# F407VET6.net
KiCad netlist of a schematic drawn in Altium Designer
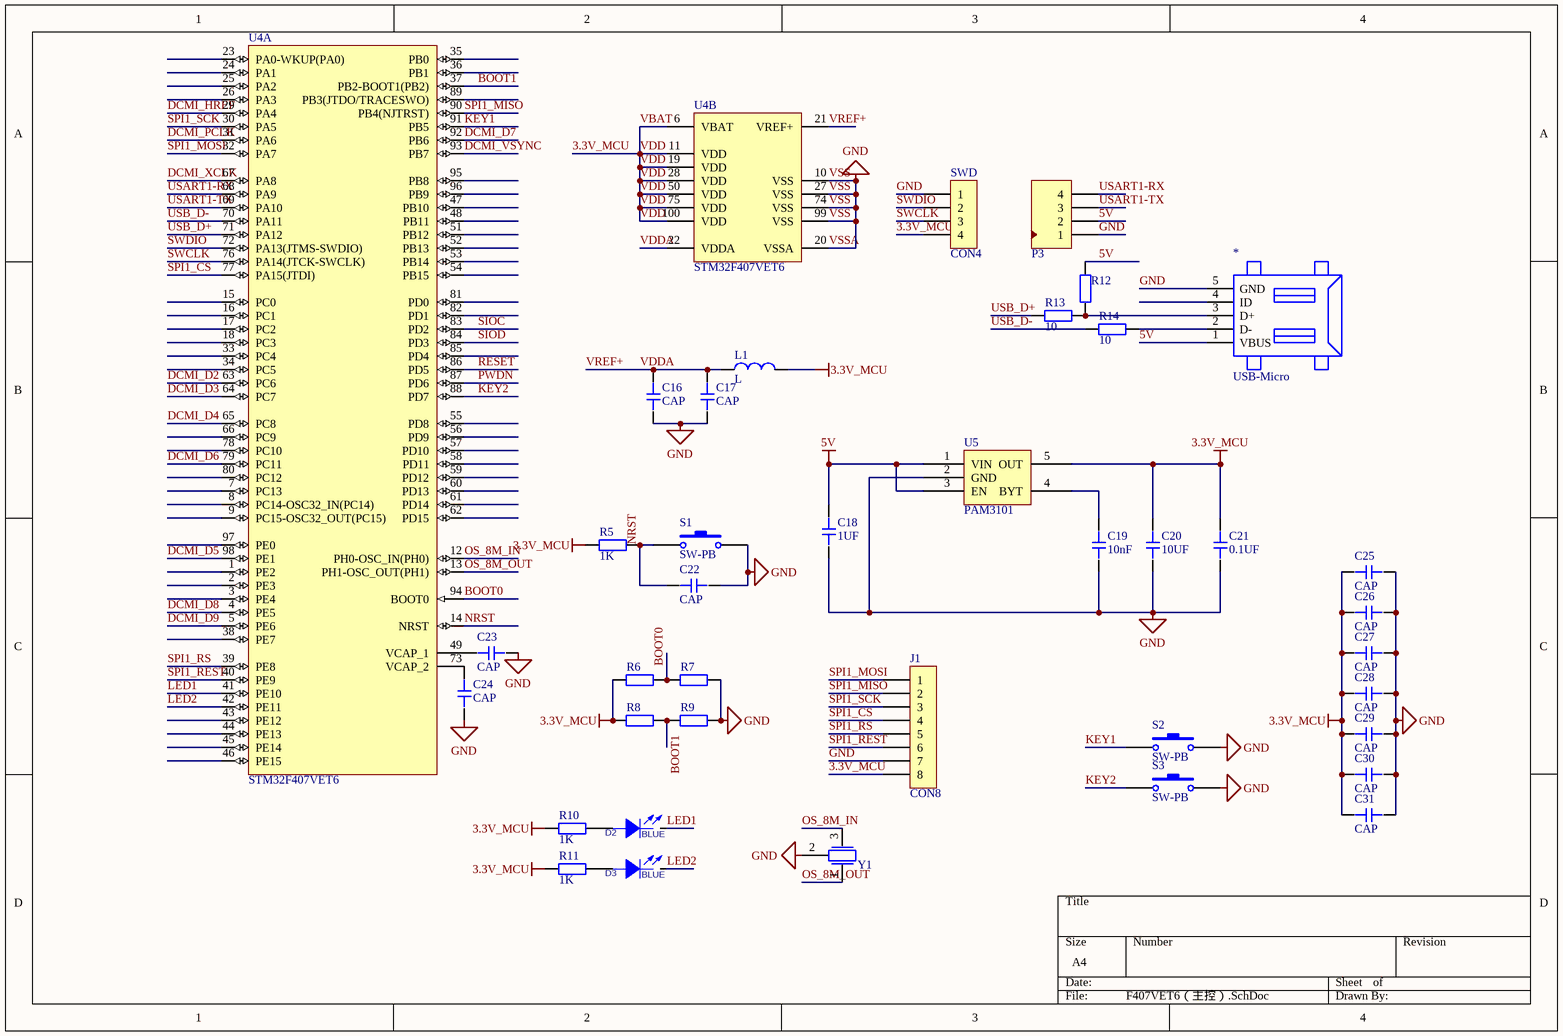
[diagram p0: F407VET6（主控）.SchDoc]

(export (version "E")
  (design (tool "Eeschema 10.0.6"))
  (components
    (comp (ref "*")
      (value "USB-Micro")
      (footprint "USB-Micro")
      (libsource (lib "XJDYJB-v1.24") (part "USB-Micro"))
    )
    (comp (ref "C16") (value "CAP") (footprint "C_0603") (libsource (lib "XJDYJB-v1.24") (part "CAP")))
    (comp (ref "C17") (value "CAP") (footprint "C_0603") (libsource (lib "XJDYJB-v1.24") (part "CAP")))
    (comp (ref "C18") (value "1UF") (footprint "C_0603") (libsource (lib "XJDYJB-v1.24") (part "CAP")))
    (comp (ref "C19") (value "10nF") (footprint "C_0603") (libsource (lib "XJDYJB-v1.24") (part "CAP")))
    (comp (ref "C20") (value "10UF") (footprint "C_0805") (libsource (lib "XJDYJB-v1.24") (part "CAP")))
    (comp (ref "C21") (value "0.1UF") (footprint "C_0603") (libsource (lib "XJDYJB-v1.24") (part "CAP")))
    (comp (ref "C22") (value "CAP") (footprint "C_0603") (libsource (lib "XJDYJB-v1.24") (part "CAP")))
    (comp (ref "C23") (value "CAP") (footprint "C_0603") (libsource (lib "XJDYJB-v1.24") (part "CAP")))
    (comp (ref "C24") (value "CAP") (footprint "C_0603") (libsource (lib "XJDYJB-v1.24") (part "CAP")))
    (comp (ref "C25") (value "CAP") (footprint "C_0603") (libsource (lib "XJDYJB-v1.24") (part "CAP")))
    (comp (ref "C26") (value "CAP") (footprint "C_0603") (libsource (lib "XJDYJB-v1.24") (part "CAP")))
    (comp (ref "C27") (value "CAP") (footprint "C_0603") (libsource (lib "XJDYJB-v1.24") (part "CAP")))
    (comp (ref "C28") (value "CAP") (footprint "C_0603") (libsource (lib "XJDYJB-v1.24") (part "CAP")))
    (comp (ref "C29") (value "CAP") (footprint "C_0603") (libsource (lib "XJDYJB-v1.24") (part "CAP")))
    (comp (ref "C30") (value "CAP") (footprint "C_0603") (libsource (lib "XJDYJB-v1.24") (part "CAP")))
    (comp (ref "C31") (value "CAP") (footprint "C_0603") (libsource (lib "XJDYJB-v1.24") (part "CAP")))
    (comp (ref "D2")
      (value "BLUE")
      (footprint "LED_0603")
      (fields (field (name "Comment") "LED"))
      (libsource (lib "XJDYJB-v1.24") (part "LED"))
    )
    (comp (ref "D3")
      (value "BLUE")
      (footprint "LED_0603")
      (fields (field (name "Comment") "LED"))
      (libsource (lib "XJDYJB-v1.24") (part "LED"))
    )
    (comp (ref "J1")
      (value "CON8")
      (footprint "sip-8")
      (description "Connector")
      (libsource (lib "接口") (part "CON8"))
    )
    (comp (ref "L1") (value "L") (footprint "L-0603") (libsource (lib "XJDYJB-v1.24") (part "L")))
    (comp (ref "P3")
      (value "Header 4")
      (footprint "HDR4*1_SH1.0")
      (description "接插件")
      (fields (field (name "PUBLISHER") "Altium Limited"))
      (libsource (lib "HDR_Fszhang") (part "Header 4"))
    )
    (comp (ref "R5")
      (value "1K")
      (footprint "0603-1")
      (description "贴片电阻")
      (fields (field (name "Comment") "Res1") (field (name "PUBLISHER") "Altium Limited"))
      (libsource (lib "Fszhang") (part "Res1"))
    )
    (comp (ref "R6")
      (value "Res1")
      (footprint "0603-1")
      (description "贴片电阻")
      (fields (field (name "PUBLISHER") "Altium Limited"))
      (libsource (lib "Fszhang") (part "Res1"))
    )
    (comp (ref "R7")
      (value "Res1")
      (footprint "0603-1")
      (description "贴片电阻")
      (fields (field (name "PUBLISHER") "Altium Limited"))
      (libsource (lib "Fszhang") (part "Res1"))
    )
    (comp (ref "R8")
      (value "Res1")
      (footprint "0603-1")
      (description "贴片电阻")
      (fields (field (name "PUBLISHER") "Altium Limited"))
      (libsource (lib "Fszhang") (part "Res1"))
    )
    (comp (ref "R9")
      (value "Res1")
      (footprint "0603-1")
      (description "贴片电阻")
      (fields (field (name "PUBLISHER") "Altium Limited"))
      (libsource (lib "Fszhang") (part "Res1"))
    )
    (comp (ref "R10")
      (value "1K")
      (footprint "0603-1")
      (description "贴片电阻")
      (fields (field (name "Comment") "Res1") (field (name "PUBLISHER") "Altium Limited"))
      (libsource (lib "Fszhang") (part "Res1"))
    )
    (comp (ref "R11")
      (value "1K")
      (footprint "0603-1")
      (description "贴片电阻")
      (fields (field (name "Comment") "Res1") (field (name "PUBLISHER") "Altium Limited"))
      (libsource (lib "Fszhang") (part "Res1"))
    )
    (comp (ref "R12")
      (value "Res1")
      (footprint "0603-1")
      (description "贴片电阻")
      (fields (field (name "PUBLISHER") "Altium Limited"))
      (libsource (lib "") (part "Res1_1"))
    )
    (comp (ref "R13")
      (value "10")
      (footprint "0603-1")
      (description "贴片电阻")
      (fields (field (name "Comment") "Res1") (field (name "PUBLISHER") "Altium Limited"))
      (libsource (lib "Fszhang") (part "Res1"))
    )
    (comp (ref "R14")
      (value "10")
      (footprint "0603-1")
      (description "贴片电阻")
      (fields (field (name "Comment") "Res1") (field (name "PUBLISHER") "Altium Limited"))
      (libsource (lib "Fszhang") (part "Res1"))
    )
    (comp (ref "S1")
      (value "SW-PB")
      (footprint "Switch-PB-C-M")
      (description "Switch")
      (fields (field (name "PUBLISHER") "Altium Limited"))
      (libsource (lib "门控服务器库文件") (part "SW-PB"))
    )
    (comp (ref "S2")
      (value "SW-PB")
      (footprint "Switch-PB-C-M")
      (description "Switch")
      (fields (field (name "PUBLISHER") "Altium Limited"))
      (libsource (lib "门控服务器库文件") (part "SW-PB"))
    )
    (comp (ref "S3")
      (value "SW-PB")
      (footprint "Switch-PB-C-M")
      (description "Switch")
      (fields (field (name "PUBLISHER") "Altium Limited"))
      (libsource (lib "门控服务器库文件") (part "SW-PB"))
    )
    (comp (ref "SWD")
      (value "CON4")
      (footprint "sip-4")
      (description "Connector")
      (libsource (lib "接口") (part "CON4"))
    )
    (comp (ref "U4")
      (value "STM32F407VET6")
      (footprint "STM-LQFP100_N")
      (fields (field (name "MANUFACTURER") "STMicroelectronics"))
      (libsource (lib "STMicroelectronics STM32 F4") (part "STM32F407VET6"))
    )
    (comp (ref "U5")
      (value "PAM3101")
      (footprint "SOT23-5")
      (description "LDO")
      (libsource (lib "XJDYJB-v1.24") (part "PAM3101"))
    )
    (comp (ref "Y1")
      (value "XTAL-3PIN")
      (footprint "X-CPX20")
      (description "贴片晶振")
      (libsource (lib "Fszhang") (part "XTAL-3PIN"))
    )
  )
  (nets
    (net (code "1") (name "/BOOT0") (class "Default")
      (node (ref "R6") (pin "2") (pinfunction "2_2") (pintype "passive"))
      (node (ref "R7") (pin "1") (pinfunction "1_1") (pintype "passive"))
      (node (ref "U4") (pin "94") (pinfunction "BOOT0_94") (pintype "input"))
    )
    (net (code "2") (name "/BOOT1") (class "Default")
      (node (ref "R8") (pin "2") (pinfunction "2_2") (pintype "passive"))
      (node (ref "R9") (pin "1") (pinfunction "1_1") (pintype "passive"))
      (node (ref "U4") (pin "37") (pinfunction "PB2-BOOT1(PB2)_37") (pintype "bidirectional"))
    )
    (net (code "3") (name "/DCMI_D2") (class "Default")
      (node (ref "U4") (pin "63") (pinfunction "PC6_63") (pintype "bidirectional"))
    )
    (net (code "4") (name "/DCMI_D3") (class "Default")
      (node (ref "U4") (pin "64") (pinfunction "PC7_64") (pintype "bidirectional"))
    )
    (net (code "5") (name "/DCMI_D4") (class "Default")
      (node (ref "U4") (pin "65") (pinfunction "PC8_65") (pintype "bidirectional"))
    )
    (net (code "6") (name "/DCMI_D5") (class "Default")
      (node (ref "U4") (pin "98") (pinfunction "PE1_98") (pintype "bidirectional"))
    )
    (net (code "7") (name "/DCMI_D6") (class "Default")
      (node (ref "U4") (pin "79") (pinfunction "PC11_79") (pintype "bidirectional"))
    )
    (net (code "8") (name "/DCMI_D7") (class "Default")
      (node (ref "U4") (pin "92") (pinfunction "PB6_92") (pintype "bidirectional"))
    )
    (net (code "9") (name "/DCMI_D8") (class "Default")
      (node (ref "U4") (pin "4") (pinfunction "PE5_4") (pintype "bidirectional"))
    )
    (net (code "10") (name "/DCMI_D9") (class "Default")
      (node (ref "U4") (pin "5") (pinfunction "PE6_5") (pintype "bidirectional"))
    )
    (net (code "11") (name "/DCMI_HREF") (class "Default")
      (node (ref "U4") (pin "29") (pinfunction "PA4_29") (pintype "bidirectional"))
    )
    (net (code "12") (name "/DCMI_PCLK") (class "Default")
      (node (ref "U4") (pin "31") (pinfunction "PA6_31") (pintype "bidirectional"))
    )
    (net (code "13") (name "/DCMI_VSYNC") (class "Default")
      (node (ref "U4") (pin "93") (pinfunction "PB7_93") (pintype "bidirectional"))
    )
    (net (code "14") (name "/DCMI_XCLK") (class "Default")
      (node (ref "U4") (pin "67") (pinfunction "PA8_67") (pintype "bidirectional"))
    )
    (net (code "15") (name "/KEY1") (class "Default")
      (node (ref "S2") (pin "1") (pinfunction "1_1") (pintype "passive"))
      (node (ref "U4") (pin "91") (pinfunction "PB5_91") (pintype "bidirectional"))
    )
    (net (code "16") (name "/KEY2") (class "Default")
      (node (ref "S3") (pin "1") (pinfunction "1_1") (pintype "passive"))
      (node (ref "U4") (pin "88") (pinfunction "PD7_88") (pintype "bidirectional"))
    )
    (net (code "17") (name "/LED1") (class "Default")
      (node (ref "D2") (pin "2") (pinfunction "CATHODE_2") (pintype "passive"))
      (node (ref "U4") (pin "41") (pinfunction "PE10_41") (pintype "bidirectional"))
    )
    (net (code "18") (name "/LED2") (class "Default")
      (node (ref "D3") (pin "2") (pinfunction "CATHODE_2") (pintype "passive"))
      (node (ref "U4") (pin "42") (pinfunction "PE11_42") (pintype "bidirectional"))
    )
    (net (code "19") (name "/NRST") (class "Default")
      (node (ref "C22") (pin "2") (pinfunction "2_2") (pintype "passive"))
      (node (ref "R5") (pin "2") (pinfunction "2_2") (pintype "passive"))
      (node (ref "S1") (pin "1") (pinfunction "1_1") (pintype "passive"))
      (node (ref "U4") (pin "14") (pinfunction "NRST_14") (pintype "bidirectional"))
    )
    (net (code "20") (name "/OS_8M_IN") (class "Default")
      (node (ref "U4") (pin "12") (pinfunction "PH0-OSC_IN(PH0)_12") (pintype "bidirectional"))
      (node (ref "Y1") (pin "3") (pinfunction "3_3") (pintype "passive"))
    )
    (net (code "21") (name "/OS_8M_OUT") (class "Default")
      (node (ref "U4") (pin "13") (pinfunction "PH1-OSC_OUT(PH1)_13") (pintype "bidirectional"))
      (node (ref "Y1") (pin "1") (pinfunction "1_1") (pintype "passive"))
    )
    (net (code "22") (name "/PWDN") (class "Default")
      (node (ref "U4") (pin "87") (pinfunction "PD6_87") (pintype "bidirectional"))
    )
    (net (code "23") (name "/RESET") (class "Default")
      (node (ref "U4") (pin "86") (pinfunction "PD5_86") (pintype "bidirectional"))
    )
    (net (code "24") (name "/SIOC") (class "Default")
      (node (ref "U4") (pin "83") (pinfunction "PD2_83") (pintype "bidirectional"))
    )
    (net (code "25") (name "/SIOD") (class "Default")
      (node (ref "U4") (pin "84") (pinfunction "PD3_84") (pintype "bidirectional"))
    )
    (net (code "26") (name "/SPI1_CS") (class "Default")
      (node (ref "J1") (pin "4") (pinfunction "4_4") (pintype "passive"))
      (node (ref "U4") (pin "77") (pinfunction "PA15(JTDI)_77") (pintype "bidirectional"))
    )
    (net (code "27") (name "/SPI1_MISO") (class "Default")
      (node (ref "J1") (pin "2") (pinfunction "2_2") (pintype "passive"))
      (node (ref "U4") (pin "90") (pinfunction "PB4(NJTRST)_90") (pintype "bidirectional"))
    )
    (net (code "28") (name "/SPI1_MOSI") (class "Default")
      (node (ref "J1") (pin "1") (pinfunction "1_1") (pintype "passive"))
      (node (ref "U4") (pin "32") (pinfunction "PA7_32") (pintype "bidirectional"))
    )
    (net (code "29") (name "/SPI1_REST") (class "Default")
      (node (ref "J1") (pin "6") (pinfunction "6_6") (pintype "passive"))
      (node (ref "U4") (pin "40") (pinfunction "PE9_40") (pintype "bidirectional"))
    )
    (net (code "30") (name "/SPI1_RS") (class "Default")
      (node (ref "J1") (pin "5") (pinfunction "5_5") (pintype "passive"))
      (node (ref "U4") (pin "39") (pinfunction "PE8_39") (pintype "bidirectional"))
    )
    (net (code "31") (name "/SPI1_SCK") (class "Default")
      (node (ref "J1") (pin "3") (pinfunction "3_3") (pintype "passive"))
      (node (ref "U4") (pin "30") (pinfunction "PA5_30") (pintype "bidirectional"))
    )
    (net (code "32") (name "/SWCLK") (class "Default")
      (node (ref "SWD") (pin "3") (pinfunction "3_3") (pintype "passive"))
      (node (ref "U4") (pin "76") (pinfunction "PA14(JTCK-SWCLK)_76") (pintype "bidirectional"))
    )
    (net (code "33") (name "/SWDIO") (class "Default")
      (node (ref "SWD") (pin "2") (pinfunction "2_2") (pintype "passive"))
      (node (ref "U4") (pin "72") (pinfunction "PA13(JTMS-SWDIO)_72") (pintype "bidirectional"))
    )
    (net (code "34") (name "/USART1-RX") (class "Default")
      (node (ref "P3") (pin "4") (pinfunction "4_4") (pintype "passive"))
      (node (ref "U4") (pin "68") (pinfunction "PA9_68") (pintype "bidirectional"))
    )
    (net (code "35") (name "/USART1-TX") (class "Default")
      (node (ref "P3") (pin "3") (pinfunction "3_3") (pintype "passive"))
      (node (ref "U4") (pin "69") (pinfunction "PA10_69") (pintype "bidirectional"))
    )
    (net (code "36") (name "/USB_D+") (class "Default")
      (node (ref "R13") (pin "1") (pinfunction "1_1") (pintype "passive"))
      (node (ref "U4") (pin "71") (pinfunction "PA12_71") (pintype "bidirectional"))
    )
    (net (code "37") (name "/USB_D-") (class "Default")
      (node (ref "R14") (pin "1") (pinfunction "1_1") (pintype "passive"))
      (node (ref "U4") (pin "70") (pinfunction "PA11_70") (pintype "bidirectional"))
    )
    (net (code "38") (name "/VDDA") (class "Default")
      (node (ref "C16") (pin "2") (pinfunction "2_2") (pintype "passive"))
      (node (ref "C17") (pin "2") (pinfunction "2_2") (pintype "passive"))
      (node (ref "L1") (pin "1") (pinfunction "1_1") (pintype "passive"))
      (node (ref "U4") (pin "21") (pinfunction "VREF+_21") (pintype "power_in"))
      (node (ref "U4") (pin "22") (pinfunction "VDDA_22") (pintype "power_in"))
    )
    (net (code "39") (name "3.3V_MCU") (class "Default")
      (node (ref "C20") (pin "2") (pinfunction "2_2") (pintype "passive"))
      (node (ref "C21") (pin "2") (pinfunction "2_2") (pintype "passive"))
      (node (ref "C25") (pin "2") (pinfunction "2_2") (pintype "passive"))
      (node (ref "C26") (pin "2") (pinfunction "2_2") (pintype "passive"))
      (node (ref "C27") (pin "2") (pinfunction "2_2") (pintype "passive"))
      (node (ref "C28") (pin "2") (pinfunction "2_2") (pintype "passive"))
      (node (ref "C29") (pin "2") (pinfunction "2_2") (pintype "passive"))
      (node (ref "C30") (pin "2") (pinfunction "2_2") (pintype "passive"))
      (node (ref "C31") (pin "2") (pinfunction "2_2") (pintype "passive"))
      (node (ref "J1") (pin "8") (pinfunction "8_8") (pintype "passive"))
      (node (ref "L1") (pin "2") (pinfunction "2_2") (pintype "passive"))
      (node (ref "R10") (pin "1") (pinfunction "1_1") (pintype "passive"))
      (node (ref "R11") (pin "1") (pinfunction "1_1") (pintype "passive"))
      (node (ref "R5") (pin "1") (pinfunction "1_1") (pintype "passive"))
      (node (ref "R6") (pin "1") (pinfunction "1_1") (pintype "passive"))
      (node (ref "R8") (pin "1") (pinfunction "1_1") (pintype "passive"))
      (node (ref "SWD") (pin "4") (pinfunction "4_4") (pintype "passive"))
      (node (ref "U4") (pin "100") (pinfunction "VDD_100") (pintype "power_in"))
      (node (ref "U4") (pin "11") (pinfunction "VDD_11") (pintype "power_in"))
      (node (ref "U4") (pin "19") (pinfunction "VDD_19") (pintype "power_in"))
      (node (ref "U4") (pin "28") (pinfunction "VDD_28") (pintype "power_in"))
      (node (ref "U4") (pin "50") (pinfunction "VDD_50") (pintype "power_in"))
      (node (ref "U4") (pin "6") (pinfunction "VBAT_6") (pintype "power_in"))
      (node (ref "U4") (pin "75") (pinfunction "VDD_75") (pintype "power_in"))
      (node (ref "U5") (pin "5") (pinfunction "OUT_5") (pintype "passive"))
    )
    (net (code "40") (name "5V") (class "Default")
      (node (ref "*") (pin "1") (pinfunction "VBUS_1") (pintype "passive"))
      (node (ref "C18") (pin "2") (pinfunction "2_2") (pintype "passive"))
      (node (ref "P3") (pin "2") (pinfunction "2_2") (pintype "passive"))
      (node (ref "R12") (pin "2") (pinfunction "2_2") (pintype "passive"))
      (node (ref "U5") (pin "1") (pinfunction "VIN_1") (pintype "passive"))
      (node (ref "U5") (pin "3") (pinfunction "EN_3") (pintype "passive"))
    )
    (net (code "41") (name "GND") (class "Default")
      (node (ref "*") (pin "5") (pinfunction "GND_5") (pintype "passive"))
      (node (ref "C16") (pin "1") (pinfunction "1_1") (pintype "passive"))
      (node (ref "C17") (pin "1") (pinfunction "1_1") (pintype "passive"))
      (node (ref "C18") (pin "1") (pinfunction "1_1") (pintype "passive"))
      (node (ref "C19") (pin "1") (pinfunction "1_1") (pintype "passive"))
      (node (ref "C20") (pin "1") (pinfunction "1_1") (pintype "passive"))
      (node (ref "C21") (pin "1") (pinfunction "1_1") (pintype "passive"))
      (node (ref "C22") (pin "1") (pinfunction "1_1") (pintype "passive"))
      (node (ref "C23") (pin "1") (pinfunction "1_1") (pintype "passive"))
      (node (ref "C24") (pin "2") (pinfunction "2_2") (pintype "passive"))
      (node (ref "C25") (pin "1") (pinfunction "1_1") (pintype "passive"))
      (node (ref "C26") (pin "1") (pinfunction "1_1") (pintype "passive"))
      (node (ref "C27") (pin "1") (pinfunction "1_1") (pintype "passive"))
      (node (ref "C28") (pin "1") (pinfunction "1_1") (pintype "passive"))
      (node (ref "C29") (pin "1") (pinfunction "1_1") (pintype "passive"))
      (node (ref "C30") (pin "1") (pinfunction "1_1") (pintype "passive"))
      (node (ref "C31") (pin "1") (pinfunction "1_1") (pintype "passive"))
      (node (ref "J1") (pin "7") (pinfunction "7_7") (pintype "passive"))
      (node (ref "P3") (pin "1") (pinfunction "1_1") (pintype "passive"))
      (node (ref "R7") (pin "2") (pinfunction "2_2") (pintype "passive"))
      (node (ref "R9") (pin "2") (pinfunction "2_2") (pintype "passive"))
      (node (ref "S1") (pin "2") (pinfunction "2_2") (pintype "passive"))
      (node (ref "S2") (pin "2") (pinfunction "2_2") (pintype "passive"))
      (node (ref "S3") (pin "2") (pinfunction "2_2") (pintype "passive"))
      (node (ref "SWD") (pin "1") (pinfunction "1_1") (pintype "passive"))
      (node (ref "U4") (pin "10") (pinfunction "VSS_10") (pintype "power_in"))
      (node (ref "U4") (pin "20") (pinfunction "VSSA_20") (pintype "power_in"))
      (node (ref "U4") (pin "27") (pinfunction "VSS_27") (pintype "power_in"))
      (node (ref "U4") (pin "74") (pinfunction "VSS_74") (pintype "power_in"))
      (node (ref "U4") (pin "99") (pinfunction "VSS_99") (pintype "power_in"))
      (node (ref "U5") (pin "2") (pinfunction "GND_2") (pintype "passive"))
      (node (ref "Y1") (pin "2") (pinfunction "2_2") (pintype "passive"))
    )
    (net (code "42") (name "Net-(*-D+)") (class "Default")
      (node (ref "*") (pin "3") (pinfunction "D+_3") (pintype "passive"))
      (node (ref "R12") (pin "1") (pinfunction "1_1") (pintype "passive"))
      (node (ref "R13") (pin "2") (pinfunction "2_2") (pintype "passive"))
    )
    (net (code "43") (name "Net-(*-D-)") (class "Default")
      (node (ref "*") (pin "2") (pinfunction "D-_2") (pintype "passive"))
      (node (ref "R14") (pin "2") (pinfunction "2_2") (pintype "passive"))
    )
    (net (code "44") (name "Net-(D2-ANODE)") (class "Default")
      (node (ref "D2") (pin "1") (pinfunction "ANODE_1") (pintype "passive"))
      (node (ref "R10") (pin "2") (pinfunction "2_2") (pintype "passive"))
    )
    (net (code "45") (name "Net-(D3-ANODE)") (class "Default")
      (node (ref "D3") (pin "1") (pinfunction "ANODE_1") (pintype "passive"))
      (node (ref "R11") (pin "2") (pinfunction "2_2") (pintype "passive"))
    )
    (net (code "46") (name "Net-(U4A-VCAP_1)") (class "Default")
      (node (ref "C23") (pin "2") (pinfunction "2_2") (pintype "passive"))
      (node (ref "U4") (pin "49") (pinfunction "VCAP_1_49") (pintype "power_in"))
    )
    (net (code "47") (name "Net-(U4A-VCAP_2)") (class "Default")
      (node (ref "C24") (pin "1") (pinfunction "1_1") (pintype "passive"))
      (node (ref "U4") (pin "73") (pinfunction "VCAP_2_73") (pintype "power_in"))
    )
    (net (code "48") (name "Net-(U5-BYT)") (class "Default")
      (node (ref "C19") (pin "2") (pinfunction "2_2") (pintype "passive"))
      (node (ref "U5") (pin "4") (pinfunction "BYT_4") (pintype "passive"))
    )
    (net (code "49") (name "unconnected-(*-ID-Pad4)") (class "Default")
      (node (ref "*") (pin "4") (pinfunction "ID_4") (pintype "passive"))
    )
    (net (code "50") (name "unconnected-(U4A-PA0-WKUP(PA0)-Pad23)") (class "Default")
      (node (ref "U4") (pin "23") (pinfunction "PA0-WKUP(PA0)_23") (pintype "bidirectional"))
    )
    (net (code "51") (name "unconnected-(U4A-PA1-Pad24)") (class "Default")
      (node (ref "U4") (pin "24") (pinfunction "PA1_24") (pintype "bidirectional"))
    )
    (net (code "52") (name "unconnected-(U4A-PA2-Pad25)") (class "Default")
      (node (ref "U4") (pin "25") (pinfunction "PA2_25") (pintype "bidirectional"))
    )
    (net (code "53") (name "unconnected-(U4A-PA3-Pad26)") (class "Default")
      (node (ref "U4") (pin "26") (pinfunction "PA3_26") (pintype "bidirectional"))
    )
    (net (code "54") (name "unconnected-(U4A-PB0-Pad35)") (class "Default")
      (node (ref "U4") (pin "35") (pinfunction "PB0_35") (pintype "bidirectional"))
    )
    (net (code "55") (name "unconnected-(U4A-PB1-Pad36)") (class "Default")
      (node (ref "U4") (pin "36") (pinfunction "PB1_36") (pintype "bidirectional"))
    )
    (net (code "56") (name "unconnected-(U4A-PB3(JTDO{slash}TRACESWO)-Pad89)") (class "Default")
      (node (ref "U4") (pin "89") (pinfunction "PB3(JTDO/TRACESWO)_89") (pintype "bidirectional"))
    )
    (net (code "57") (name "unconnected-(U4A-PB8-Pad95)") (class "Default")
      (node (ref "U4") (pin "95") (pinfunction "PB8_95") (pintype "bidirectional"))
    )
    (net (code "58") (name "unconnected-(U4A-PB9-Pad96)") (class "Default")
      (node (ref "U4") (pin "96") (pinfunction "PB9_96") (pintype "bidirectional"))
    )
    (net (code "59") (name "unconnected-(U4A-PB10-Pad47)") (class "Default")
      (node (ref "U4") (pin "47") (pinfunction "PB10_47") (pintype "bidirectional"))
    )
    (net (code "60") (name "unconnected-(U4A-PB11-Pad48)") (class "Default")
      (node (ref "U4") (pin "48") (pinfunction "PB11_48") (pintype "bidirectional"))
    )
    (net (code "61") (name "unconnected-(U4A-PB12-Pad51)") (class "Default")
      (node (ref "U4") (pin "51") (pinfunction "PB12_51") (pintype "bidirectional"))
    )
    (net (code "62") (name "unconnected-(U4A-PB13-Pad52)") (class "Default")
      (node (ref "U4") (pin "52") (pinfunction "PB13_52") (pintype "bidirectional"))
    )
    (net (code "63") (name "unconnected-(U4A-PB14-Pad53)") (class "Default")
      (node (ref "U4") (pin "53") (pinfunction "PB14_53") (pintype "bidirectional"))
    )
    (net (code "64") (name "unconnected-(U4A-PB15-Pad54)") (class "Default")
      (node (ref "U4") (pin "54") (pinfunction "PB15_54") (pintype "bidirectional"))
    )
    (net (code "65") (name "unconnected-(U4A-PC0-Pad15)") (class "Default")
      (node (ref "U4") (pin "15") (pinfunction "PC0_15") (pintype "bidirectional"))
    )
    (net (code "66") (name "unconnected-(U4A-PC1-Pad16)") (class "Default")
      (node (ref "U4") (pin "16") (pinfunction "PC1_16") (pintype "bidirectional"))
    )
    (net (code "67") (name "unconnected-(U4A-PC2-Pad17)") (class "Default")
      (node (ref "U4") (pin "17") (pinfunction "PC2_17") (pintype "bidirectional"))
    )
    (net (code "68") (name "unconnected-(U4A-PC3-Pad18)") (class "Default")
      (node (ref "U4") (pin "18") (pinfunction "PC3_18") (pintype "bidirectional"))
    )
    (net (code "69") (name "unconnected-(U4A-PC4-Pad33)") (class "Default")
      (node (ref "U4") (pin "33") (pinfunction "PC4_33") (pintype "bidirectional"))
    )
    (net (code "70") (name "unconnected-(U4A-PC5-Pad34)") (class "Default")
      (node (ref "U4") (pin "34") (pinfunction "PC5_34") (pintype "bidirectional"))
    )
    (net (code "71") (name "unconnected-(U4A-PC9-Pad66)") (class "Default")
      (node (ref "U4") (pin "66") (pinfunction "PC9_66") (pintype "bidirectional"))
    )
    (net (code "72") (name "unconnected-(U4A-PC10-Pad78)") (class "Default")
      (node (ref "U4") (pin "78") (pinfunction "PC10_78") (pintype "bidirectional"))
    )
    (net (code "73") (name "unconnected-(U4A-PC12-Pad80)") (class "Default")
      (node (ref "U4") (pin "80") (pinfunction "PC12_80") (pintype "bidirectional"))
    )
    (net (code "74") (name "unconnected-(U4A-PC13-Pad7)") (class "Default")
      (node (ref "U4") (pin "7") (pinfunction "PC13_7") (pintype "bidirectional"))
    )
    (net (code "75") (name "unconnected-(U4A-PC14-OSC32_IN(PC14)-Pad8)") (class "Default")
      (node (ref "U4") (pin "8") (pinfunction "PC14-OSC32_IN(PC14)_8") (pintype "bidirectional"))
    )
    (net (code "76") (name "unconnected-(U4A-PC15-OSC32_OUT(PC15)-Pad9)") (class "Default")
      (node (ref "U4") (pin "9") (pinfunction "PC15-OSC32_OUT(PC15)_9") (pintype "bidirectional"))
    )
    (net (code "77") (name "unconnected-(U4A-PD0-Pad81)") (class "Default")
      (node (ref "U4") (pin "81") (pinfunction "PD0_81") (pintype "bidirectional"))
    )
    (net (code "78") (name "unconnected-(U4A-PD1-Pad82)") (class "Default")
      (node (ref "U4") (pin "82") (pinfunction "PD1_82") (pintype "bidirectional"))
    )
    (net (code "79") (name "unconnected-(U4A-PD4-Pad85)") (class "Default")
      (node (ref "U4") (pin "85") (pinfunction "PD4_85") (pintype "bidirectional"))
    )
    (net (code "80") (name "unconnected-(U4A-PD8-Pad55)") (class "Default")
      (node (ref "U4") (pin "55") (pinfunction "PD8_55") (pintype "bidirectional"))
    )
    (net (code "81") (name "unconnected-(U4A-PD9-Pad56)") (class "Default")
      (node (ref "U4") (pin "56") (pinfunction "PD9_56") (pintype "bidirectional"))
    )
    (net (code "82") (name "unconnected-(U4A-PD10-Pad57)") (class "Default")
      (node (ref "U4") (pin "57") (pinfunction "PD10_57") (pintype "bidirectional"))
    )
    (net (code "83") (name "unconnected-(U4A-PD11-Pad58)") (class "Default")
      (node (ref "U4") (pin "58") (pinfunction "PD11_58") (pintype "bidirectional"))
    )
    (net (code "84") (name "unconnected-(U4A-PD12-Pad59)") (class "Default")
      (node (ref "U4") (pin "59") (pinfunction "PD12_59") (pintype "bidirectional"))
    )
    (net (code "85") (name "unconnected-(U4A-PD13-Pad60)") (class "Default")
      (node (ref "U4") (pin "60") (pinfunction "PD13_60") (pintype "bidirectional"))
    )
    (net (code "86") (name "unconnected-(U4A-PD14-Pad61)") (class "Default")
      (node (ref "U4") (pin "61") (pinfunction "PD14_61") (pintype "bidirectional"))
    )
    (net (code "87") (name "unconnected-(U4A-PD15-Pad62)") (class "Default")
      (node (ref "U4") (pin "62") (pinfunction "PD15_62") (pintype "bidirectional"))
    )
    (net (code "88") (name "unconnected-(U4A-PE0-Pad97)") (class "Default")
      (node (ref "U4") (pin "97") (pinfunction "PE0_97") (pintype "bidirectional"))
    )
    (net (code "89") (name "unconnected-(U4A-PE2-Pad1)") (class "Default")
      (node (ref "U4") (pin "1") (pinfunction "PE2_1") (pintype "bidirectional"))
    )
    (net (code "90") (name "unconnected-(U4A-PE3-Pad2)") (class "Default")
      (node (ref "U4") (pin "2") (pinfunction "PE3_2") (pintype "bidirectional"))
    )
    (net (code "91") (name "unconnected-(U4A-PE4-Pad3)") (class "Default")
      (node (ref "U4") (pin "3") (pinfunction "PE4_3") (pintype "bidirectional"))
    )
    (net (code "92") (name "unconnected-(U4A-PE7-Pad38)") (class "Default")
      (node (ref "U4") (pin "38") (pinfunction "PE7_38") (pintype "bidirectional"))
    )
    (net (code "93") (name "unconnected-(U4A-PE12-Pad43)") (class "Default")
      (node (ref "U4") (pin "43") (pinfunction "PE12_43") (pintype "bidirectional"))
    )
    (net (code "94") (name "unconnected-(U4A-PE13-Pad44)") (class "Default")
      (node (ref "U4") (pin "44") (pinfunction "PE13_44") (pintype "bidirectional"))
    )
    (net (code "95") (name "unconnected-(U4A-PE14-Pad45)") (class "Default")
      (node (ref "U4") (pin "45") (pinfunction "PE14_45") (pintype "bidirectional"))
    )
    (net (code "96") (name "unconnected-(U4A-PE15-Pad46)") (class "Default")
      (node (ref "U4") (pin "46") (pinfunction "PE15_46") (pintype "bidirectional"))
    )
  )
)
